# eth_a.net
KiCad netlist of a schematic drawn in Altium Designer
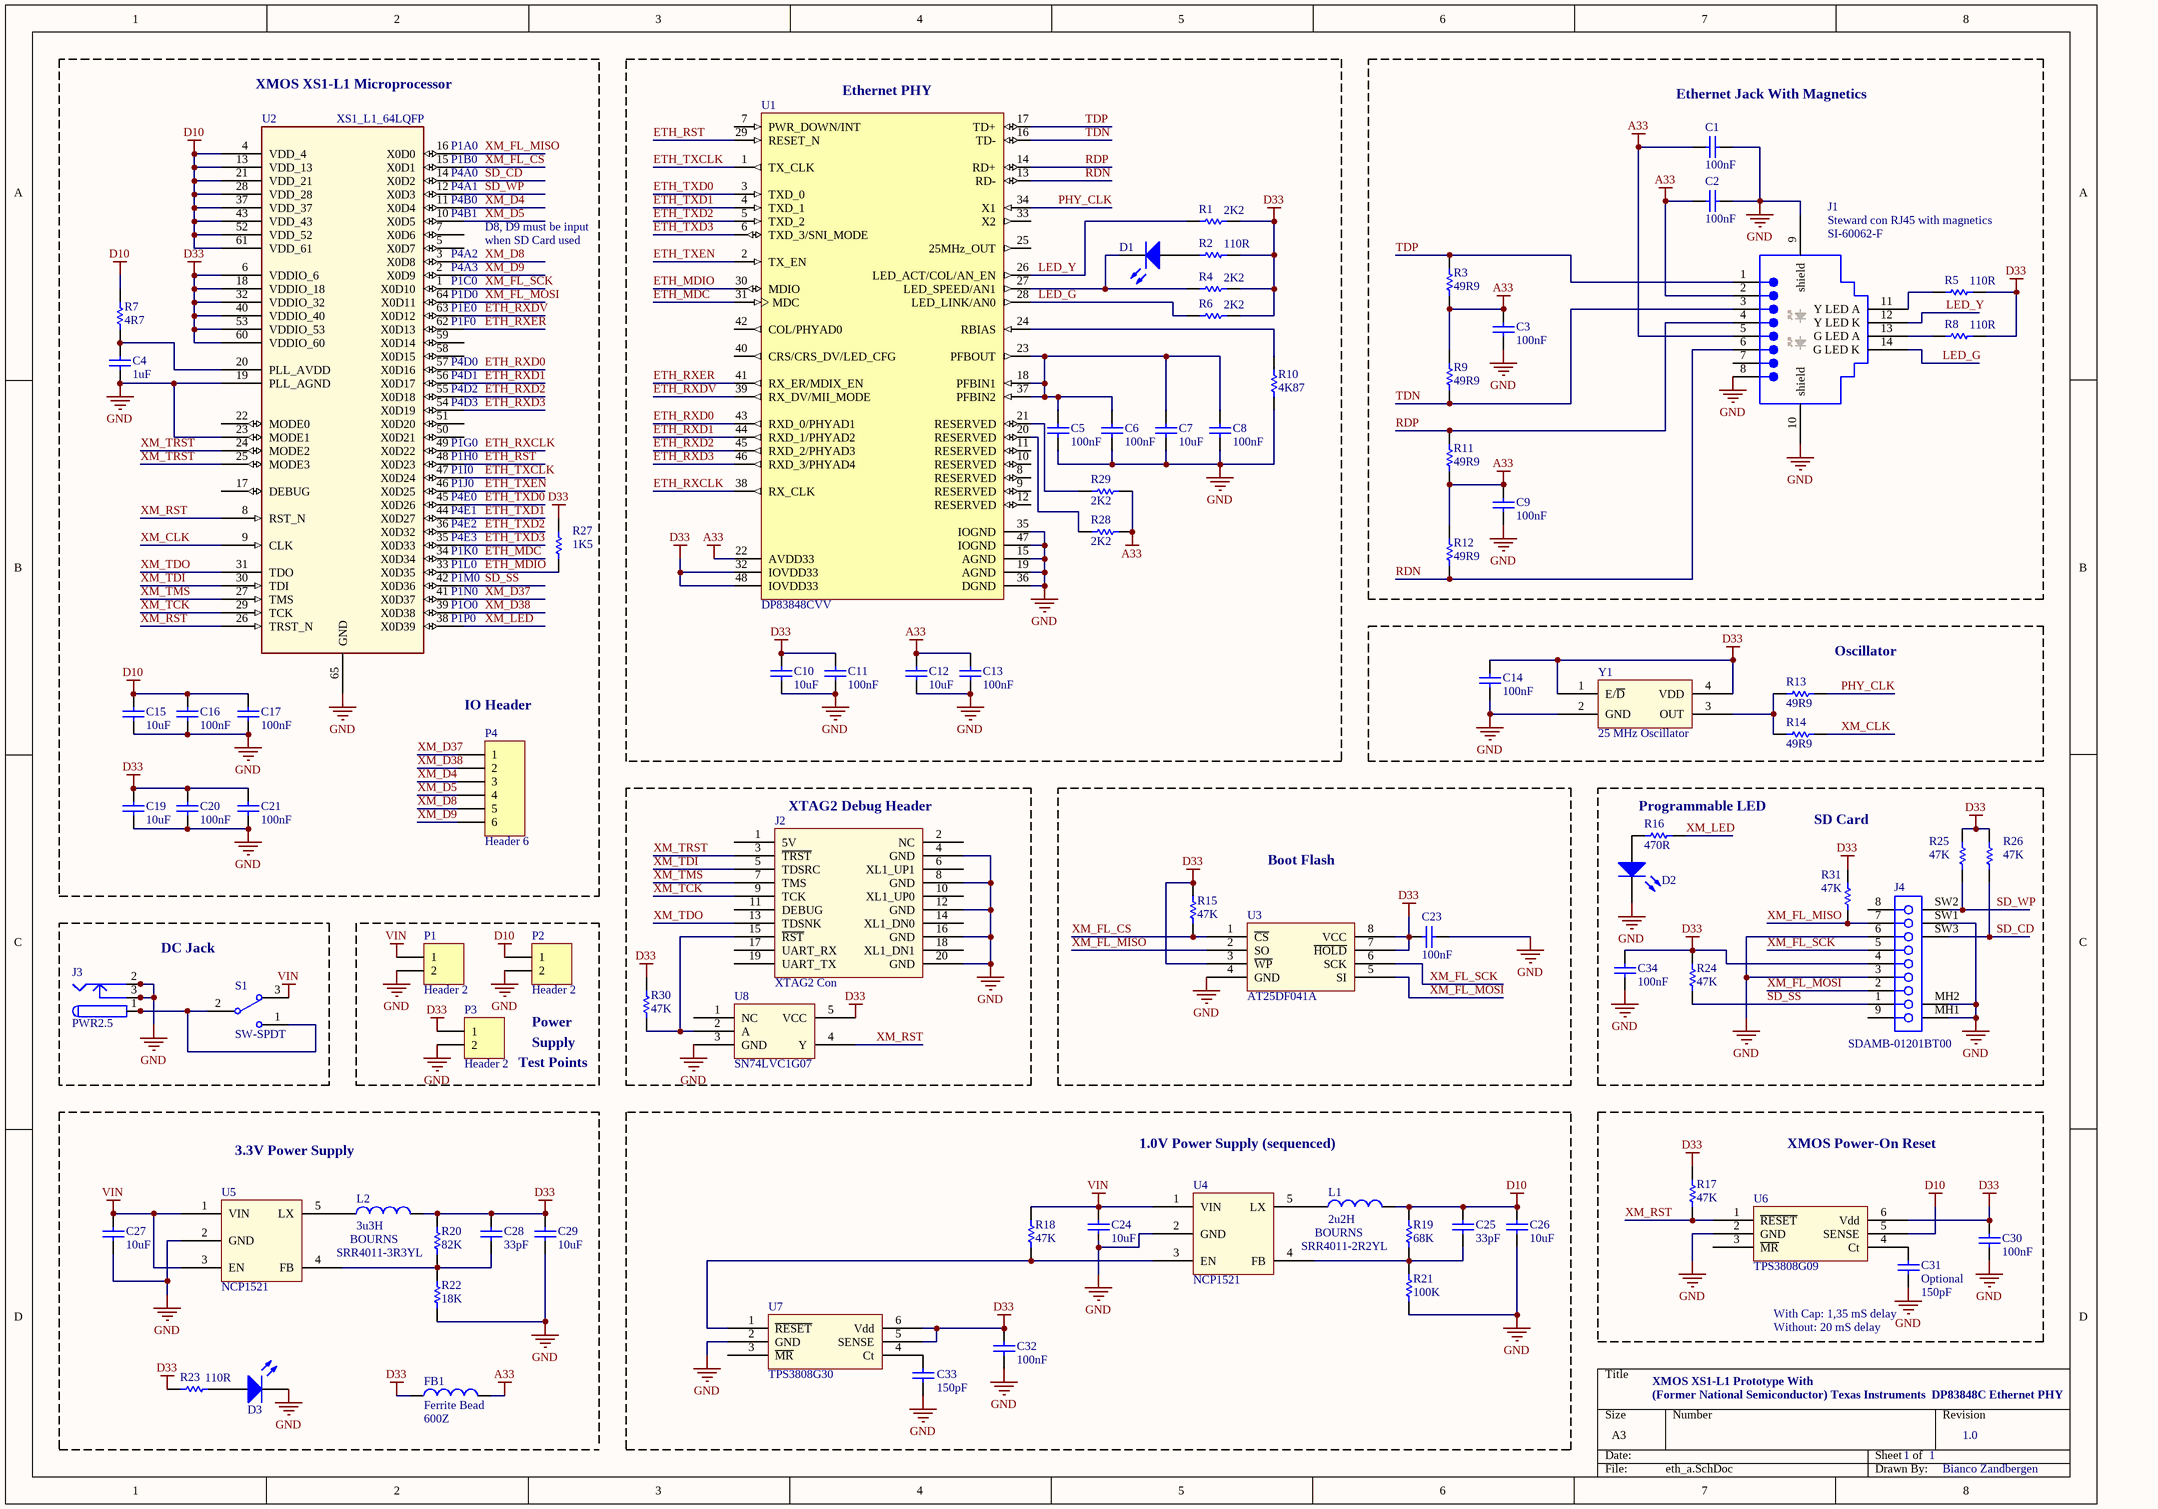
[diagram p0: eth_a.SchDoc]

(export (version "E")
  (design (tool "Eeschema 10.0.6"))
  (components
    (comp (ref "C1")
      (value "100nF")
      (footprint "1608[0603]_CAP")
      (description "Capacitor")
      (fields (field (name "Comment") "Cap"))
      (libsource (lib "xmos_common") (part "Cap"))
    )
    (comp (ref "C2")
      (value "100nF")
      (footprint "1608[0603]_CAP")
      (description "Capacitor")
      (fields (field (name "Comment") "Cap"))
      (libsource (lib "xmos_common") (part "Cap"))
    )
    (comp (ref "C3")
      (value "100nF")
      (footprint "1608[0603]_CAP")
      (description "Capacitor")
      (fields (field (name "Comment") "Cap"))
      (libsource (lib "xmos_common") (part "Cap"))
    )
    (comp (ref "C4")
      (value "1uF")
      (footprint "1608[0603]_CAP")
      (description "Capacitor")
      (fields (field (name "MANUFACTURER") "KEMET") (field (name "Comment") "Cap"))
      (libsource (lib "xmos_common") (part "Cap"))
    )
    (comp (ref "C5")
      (value "100nF")
      (footprint "1608[0603]_CAP")
      (description "Capacitor")
      (fields (field (name "Comment") "Cap"))
      (libsource (lib "xmos_common") (part "Cap"))
    )
    (comp (ref "C6")
      (value "100nF")
      (footprint "1608[0603]_CAP")
      (description "Capacitor")
      (fields (field (name "Comment") "Cap"))
      (libsource (lib "xmos_common") (part "Cap"))
    )
    (comp (ref "C7")
      (value "10uF")
      (footprint "2012[0805]_CAP")
      (description "Capacitor")
      (fields (field (name "Comment") "Cap"))
      (libsource (lib "xmos_common") (part "Cap"))
    )
    (comp (ref "C8")
      (value "100nF")
      (footprint "1608[0603]_CAP")
      (description "Capacitor")
      (fields (field (name "Comment") "Cap"))
      (libsource (lib "xmos_common") (part "Cap"))
    )
    (comp (ref "C9")
      (value "100nF")
      (footprint "1608[0603]_CAP")
      (description "Capacitor")
      (fields (field (name "Comment") "Cap"))
      (libsource (lib "xmos_common") (part "Cap"))
    )
    (comp (ref "C10")
      (value "10uF")
      (footprint "2012[0805]_CAP")
      (description "Capacitor")
      (fields (field (name "Comment") "Cap"))
      (libsource (lib "xmos_common") (part "Cap"))
    )
    (comp (ref "C11")
      (value "100nF")
      (footprint "1608[0603]_CAP")
      (description "Capacitor")
      (fields (field (name "Comment") "Cap"))
      (libsource (lib "xmos_common") (part "Cap"))
    )
    (comp (ref "C12")
      (value "10uF")
      (footprint "2012[0805]_CAP")
      (description "Capacitor")
      (fields (field (name "Comment") "Cap"))
      (libsource (lib "xmos_common") (part "Cap"))
    )
    (comp (ref "C13")
      (value "100nF")
      (footprint "1608[0603]_CAP")
      (description "Capacitor")
      (fields (field (name "Comment") "Cap"))
      (libsource (lib "xmos_common") (part "Cap"))
    )
    (comp (ref "C14")
      (value "100nF")
      (footprint "1608[0603]_CAP")
      (description "Capacitor")
      (fields (field (name "Comment") "Cap"))
      (libsource (lib "xmos_common") (part "Cap"))
    )
    (comp (ref "C15")
      (value "10uF")
      (footprint "2012[0805]_CAP")
      (description "Capacitor")
      (fields (field (name "MANUFACTURER") "AVX") (field (name "Comment") "Cap"))
      (libsource (lib "xmos_common") (part "Cap"))
    )
    (comp (ref "C16")
      (value "100nF")
      (footprint "1608[0603]_CAP")
      (description "Capacitor")
      (fields (field (name "MANUFACTURER") "MURATA") (field (name "Comment") "Cap"))
      (libsource (lib "xmos_common") (part "Cap"))
    )
    (comp (ref "C17")
      (value "100nF")
      (footprint "1608[0603]_CAP")
      (description "Capacitor")
      (fields (field (name "Comment") "Cap"))
      (libsource (lib "xmos_common") (part "Cap"))
    )
    (comp (ref "C19")
      (value "10uF")
      (footprint "2012[0805]_CAP")
      (description "Capacitor")
      (fields (field (name "Comment") "Cap"))
      (libsource (lib "xmos_common") (part "Cap"))
    )
    (comp (ref "C20")
      (value "100nF")
      (footprint "1608[0603]_CAP")
      (description "Capacitor")
      (fields (field (name "Comment") "Cap"))
      (libsource (lib "xmos_common") (part "Cap"))
    )
    (comp (ref "C21")
      (value "100nF")
      (footprint "1608[0603]_CAP")
      (description "Capacitor")
      (fields (field (name "Comment") "Cap"))
      (libsource (lib "xmos_common") (part "Cap"))
    )
    (comp (ref "C23")
      (value "100nF")
      (footprint "1608[0603]_CAP")
      (description "Capacitor")
      (fields (field (name "Comment") "Cap"))
      (libsource (lib "xmos_common") (part "Cap"))
    )
    (comp (ref "C24")
      (value "10uF")
      (footprint "2012[0805]_CAP")
      (description "Capacitor")
      (fields (field (name "Comment") "Cap"))
      (libsource (lib "xmos_common") (part "Cap"))
    )
    (comp (ref "C25")
      (value "33pF")
      (footprint "1608[0603]_CAP")
      (description "Capacitor")
      (fields (field (name "Comment") "Cap"))
      (libsource (lib "xmos_common") (part "Cap"))
    )
    (comp (ref "C26")
      (value "10uF")
      (footprint "2012[0805]_CAP")
      (description "Capacitor")
      (fields (field (name "Comment") "Cap"))
      (libsource (lib "xmos_common") (part "Cap"))
    )
    (comp (ref "C27")
      (value "10uF")
      (footprint "2012[0805]_CAP")
      (description "Capacitor")
      (fields (field (name "Comment") "Cap"))
      (libsource (lib "xmos_common") (part "Cap"))
    )
    (comp (ref "C28")
      (value "33pF")
      (footprint "1608[0603]_CAP")
      (description "Capacitor")
      (fields (field (name "MANUFACTURER") "MURATA") (field (name "Comment") "Cap"))
      (libsource (lib "xmos_common") (part "Cap"))
    )
    (comp (ref "C29")
      (value "10uF")
      (footprint "2012[0805]_CAP")
      (description "Capacitor")
      (fields (field (name "Comment") "Cap"))
      (libsource (lib "xmos_common") (part "Cap"))
    )
    (comp (ref "C30")
      (value "100nF")
      (footprint "1608[0603]_CAP")
      (description "Capacitor")
      (fields (field (name "Comment") "Cap"))
      (libsource (lib "xmos_common") (part "Cap"))
    )
    (comp (ref "C31")
      (value "Optional")
      (footprint "1608[0603]_CAP")
      (description "Capacitor")
      (fields (field (name "ALTIUM_VALUE") "150pF") (field (name "MANUFACTURER") "MURATA"))
      (libsource (lib "xmos_common") (part "Cap"))
    )
    (comp (ref "C32")
      (value "100nF")
      (footprint "1608[0603]_CAP")
      (description "Capacitor")
      (fields (field (name "Comment") "Cap"))
      (libsource (lib "xmos_common") (part "Cap"))
    )
    (comp (ref "C33")
      (value "150pF")
      (footprint "1608[0603]_CAP")
      (description "Capacitor")
      (fields (field (name "Comment") "Optional"))
      (libsource (lib "xmos_common") (part "Cap"))
    )
    (comp (ref "C34")
      (value "100nF")
      (footprint "1608[0603]_CAP")
      (description "Capacitor")
      (fields (field (name "Comment") "Cap"))
      (libsource (lib "xmos_common") (part "Cap"))
    )
    (comp (ref "D1")
      (value "LED3")
      (footprint "2012[0805]_LED")
      (description "SMD LED 0805")
      (fields (field (name "MANUFACTURER") "KINGBRIGHT"))
      (libsource (lib "xmos_common") (part "LED3"))
    )
    (comp (ref "D2")
      (value "LED3")
      (footprint "2012[0805]_LED")
      (description "SMD LED 0805")
      (libsource (lib "xmos_common") (part "LED3"))
    )
    (comp (ref "D3")
      (value "LED3")
      (footprint "2012[0805]_LED")
      (description "SMD LED 0805")
      (fields (field (name "MANUFACTURER") "KINGBRIGHT"))
      (libsource (lib "xmos_common") (part "LED3"))
    )
    (comp (ref "FB1")
      (value "Ferrite Bead")
      (footprint "1608[0603]_FB")
      (fields (field (name "ALTIUM_VALUE") "600Z") (field (name "MANUFACTURER") "MURATA"))
      (libsource (lib "xmos_common") (part "Ferrite Bead"))
    )
    (comp (ref "J1")
      (value "Steward con RJ45 with magnetics")
      (footprint "Steward Con RJ45")
      (description "Right Angle,RJ45-Keyed, Flange Mount PCB Jack")
      (fields (field (name "DETAILS") "SI-60062-F") (field (name "MANUFACTURER") "STEWART CONNECTOR"))
      (libsource (lib "xmos_common") (part "Steward con RJ45 with magnetics"))
    )
    (comp (ref "J2")
      (value "XTAG2 Con")
      (footprint "IDC2.54-V20D")
      (description "XTAG2 Connector")
      (fields (field (name "MANUFACTURER") "TYCO"))
      (libsource (lib "xmos_common") (part "XTAG2_CON"))
    )
    (comp (ref "J3")
      (value "PWR2.5")
      (footprint "KLD-0202")
      (description "Low Voltage Power Supply Connector")
      (fields (field (name "MANUFACTURER") "SWITCHCRAFT"))
      (libsource (lib "xmos_common") (part "PWR2.5"))
    )
    (comp (ref "J4")
      (value "SDAMB-01201BT00")
      (footprint "SDCARD-SDAMB-012")
      (description "Secure Digital Card Connector, Type A without Cover")
      (fields (field (name "MANUFACTURER") "MULTICOMP"))
      (libsource (lib "xmos_common") (part "SDAMB-01201BT00"))
    )
    (comp (ref "L1")
      (value "2u2H")
      (footprint "BOURNS_SRR4011")
      (description "Inductor")
      (fields (field (name "MANUFACTURER") "BOURNS") (field (name "PRODUCTCODE") "SRR4011-2R2YL"))
      (libsource (lib "xmos_common") (part "Inductor"))
    )
    (comp (ref "L2")
      (value "3u3H")
      (footprint "BOURNS_SRR4011")
      (description "Inductor")
      (fields (field (name "PRODUCTCODE") "SRR4011-3R3YL") (field (name "MANUFACTURER") "BOURNS"))
      (libsource (lib "xmos_common") (part "Inductor"))
    )
    (comp (ref "P1")
      (value "Header 2")
      (footprint "HDR1X2")
      (description "Header, 2-Pin")
      (libsource (lib "xmos_common") (part "Header 2"))
    )
    (comp (ref "P2")
      (value "Header 2")
      (footprint "HDR1X2")
      (description "Header, 2-Pin")
      (libsource (lib "xmos_common") (part "Header 2"))
    )
    (comp (ref "P3")
      (value "Header 2")
      (footprint "HDR1X2")
      (description "Header, 2-Pin")
      (libsource (lib "xmos_common") (part "Header 2"))
    )
    (comp (ref "P4")
      (value "Header 6")
      (footprint "HDR1X6")
      (description "Header, 6-Pin")
      (libsource (lib "xmos_common") (part "Header 6"))
    )
    (comp (ref "R1")
      (value "2K2")
      (footprint "1608[0603]_RES")
      (description "Resistor")
      (fields (field (name "MANUFACTURER") "YAGEO") (field (name "Comment") "Res"))
      (libsource (lib "xmos_common") (part "Res"))
    )
    (comp (ref "R2")
      (value "110R")
      (footprint "1608[0603]_RES")
      (description "Resistor")
      (fields (field (name "Comment") "Res"))
      (libsource (lib "xmos_common") (part "Res"))
    )
    (comp (ref "R3")
      (value "49R9")
      (footprint "1608[0603]_RES")
      (description "Resistor")
      (fields (field (name "MANUFACTURER") "SUSUMU") (field (name "Comment") "Res"))
      (libsource (lib "xmos_common") (part "Res"))
    )
    (comp (ref "R4")
      (value "2K2")
      (footprint "1608[0603]_RES")
      (description "Resistor")
      (fields (field (name "Comment") "Res"))
      (libsource (lib "xmos_common") (part "Res"))
    )
    (comp (ref "R5")
      (value "110R")
      (footprint "1608[0603]_RES")
      (description "Resistor")
      (fields (field (name "MANUFACTURER") "PANASONIC") (field (name "Comment") "Res"))
      (libsource (lib "xmos_common") (part "Res"))
    )
    (comp (ref "R6")
      (value "2K2")
      (footprint "1608[0603]_RES")
      (description "Resistor")
      (fields (field (name "Comment") "Res"))
      (libsource (lib "xmos_common") (part "Res"))
    )
    (comp (ref "R7")
      (value "4R7")
      (footprint "1608[0603]_RES")
      (description "Resistor")
      (fields (field (name "MANUFACTURER") "PANASONIC") (field (name "Comment") "Res"))
      (libsource (lib "xmos_common") (part "Res"))
    )
    (comp (ref "R8")
      (value "110R")
      (footprint "1608[0603]_RES")
      (description "Resistor")
      (fields (field (name "Comment") "Res"))
      (libsource (lib "xmos_common") (part "Res"))
    )
    (comp (ref "R9")
      (value "49R9")
      (footprint "1608[0603]_RES")
      (description "Resistor")
      (fields (field (name "Comment") "Res"))
      (libsource (lib "xmos_common") (part "Res"))
    )
    (comp (ref "R10")
      (value "4K87")
      (footprint "1608[0603]_RES")
      (description "Resistor")
      (fields (field (name "MANUFACTURER") "MULTICOMP") (field (name "Comment") "Res"))
      (libsource (lib "xmos_common") (part "Res"))
    )
    (comp (ref "R11")
      (value "49R9")
      (footprint "1608[0603]_RES")
      (description "Resistor")
      (fields (field (name "Comment") "Res"))
      (libsource (lib "xmos_common") (part "Res"))
    )
    (comp (ref "R12")
      (value "49R9")
      (footprint "1608[0603]_RES")
      (description "Resistor")
      (fields (field (name "Comment") "Res"))
      (libsource (lib "xmos_common") (part "Res"))
    )
    (comp (ref "R13")
      (value "49R9")
      (footprint "1608[0603]_RES")
      (description "Resistor")
      (fields (field (name "Comment") "Res"))
      (libsource (lib "xmos_common") (part "Res"))
    )
    (comp (ref "R14")
      (value "49R9")
      (footprint "1608[0603]_RES")
      (description "Resistor")
      (fields (field (name "Comment") "Res"))
      (libsource (lib "xmos_common") (part "Res"))
    )
    (comp (ref "R15")
      (value "47K")
      (footprint "1608[0603]_RES")
      (description "Resistor")
      (fields (field (name "MANUFACTURER") "VISHAY DRALORIC") (field (name "Comment") "Res"))
      (libsource (lib "xmos_common") (part "Res"))
    )
    (comp (ref "R16")
      (value "470R")
      (footprint "1608[0603]_RES")
      (description "Resistor")
      (fields (field (name "MANUFACTURER") "BOURNS") (field (name "Comment") "Res"))
      (libsource (lib "xmos_common") (part "Res"))
    )
    (comp (ref "R17")
      (value "47K")
      (footprint "1608[0603]_RES")
      (description "Resistor")
      (fields (field (name "Comment") "Res"))
      (libsource (lib "xmos_common") (part "Res"))
    )
    (comp (ref "R18")
      (value "47K")
      (footprint "1608[0603]_RES")
      (description "Resistor")
      (fields (field (name "Comment") "Res"))
      (libsource (lib "xmos_common") (part "Res"))
    )
    (comp (ref "R19")
      (value "68K")
      (footprint "1608[0603]_RES")
      (description "Resistor")
      (fields (field (name "MANUFACTURER") "PANASONIC") (field (name "Comment") "Res"))
      (libsource (lib "xmos_common") (part "Res"))
    )
    (comp (ref "R20")
      (value "82K")
      (footprint "1608[0603]_RES")
      (description "Resistor")
      (fields (field (name "MANUFACTURER") "VISHAY DRALORIC") (field (name "Comment") "Res"))
      (libsource (lib "xmos_common") (part "Res"))
    )
    (comp (ref "R21")
      (value "100K")
      (footprint "1608[0603]_RES")
      (description "Resistor")
      (fields (field (name "MANUFACTURER") "VISHAY DRALORIC") (field (name "Comment") "Res"))
      (libsource (lib "xmos_common") (part "Res"))
    )
    (comp (ref "R22")
      (value "18K")
      (footprint "1608[0603]_RES")
      (description "Resistor")
      (fields (field (name "MANUFACTURER") "VISHAY DRALORIC") (field (name "Comment") "Res"))
      (libsource (lib "xmos_common") (part "Res"))
    )
    (comp (ref "R23")
      (value "110R")
      (footprint "1608[0603]_RES")
      (description "Resistor")
      (fields (field (name "Comment") "Res"))
      (libsource (lib "xmos_common") (part "Res"))
    )
    (comp (ref "R24")
      (value "47K")
      (footprint "1608[0603]_RES")
      (description "Resistor")
      (fields (field (name "Comment") "Res"))
      (libsource (lib "xmos_common") (part "Res"))
    )
    (comp (ref "R25")
      (value "47K")
      (footprint "1608[0603]_RES")
      (description "Resistor")
      (fields (field (name "Comment") "Res"))
      (libsource (lib "xmos_common") (part "Res"))
    )
    (comp (ref "R26")
      (value "47K")
      (footprint "1608[0603]_RES")
      (description "Resistor")
      (fields (field (name "Comment") "Res"))
      (libsource (lib "xmos_common") (part "Res"))
    )
    (comp (ref "R27")
      (value "1K5")
      (footprint "1608[0603]_RES")
      (description "Resistor")
      (fields (field (name "MANUFACTURER") "PANASONIC") (field (name "Comment") "Res"))
      (libsource (lib "xmos_common") (part "Res"))
    )
    (comp (ref "R28")
      (value "2K2")
      (footprint "1608[0603]_RES")
      (description "Resistor")
      (fields (field (name "Comment") "Res"))
      (libsource (lib "xmos_common") (part "Res"))
    )
    (comp (ref "R29")
      (value "2K2")
      (footprint "1608[0603]_RES")
      (description "Resistor")
      (fields (field (name "Comment") "Res"))
      (libsource (lib "xmos_common") (part "Res"))
    )
    (comp (ref "R30")
      (value "47K")
      (footprint "1608[0603]_RES")
      (description "Resistor")
      (fields (field (name "Comment") "Res"))
      (libsource (lib "xmos_common") (part "Res"))
    )
    (comp (ref "R31")
      (value "47K")
      (footprint "1608[0603]_RES")
      (description "Resistor")
      (fields (field (name "Comment") "Res"))
      (libsource (lib "xmos_common") (part "Res"))
    )
    (comp (ref "S1")
      (value "SW-SPDT")
      (footprint "SIP-3")
      (description "SPDT Switch")
      (fields (field (name "MANUFACTURER") "EAO"))
      (libsource (lib "xmos_common") (part "SW-SPDT"))
    )
    (comp (ref "U1")
      (value "DP83848CVV")
      (footprint "TSQFP50P900X900-48M")
      (description "Single Port 10/100 Mb/s Ethernet PHY")
      (fields (field (name "MANUFACTURER") "National Semiconductor"))
      (libsource (lib "xmos_common") (part "DP83848CVV"))
    )
    (comp (ref "U2")
      (value "XS1_L1_64LQFP")
      (footprint "XMOS_QFP50P1200X1200X160-65N")
      (description "XMOS XS1-L1 Microprocessor")
      (fields (field (name "MANUFACTURER") "XMOS"))
      (libsource (lib "xmos_common") (part "XS1_L1_64LQFP"))
    )
    (comp (ref "U3")
      (value "AT25DF041A")
      (footprint "SOIC150-8_M")
      (description "4Mbit SPI Flash")
      (fields (field (name "MANUFACTURER") "ATMEL"))
      (libsource (lib "xmos_common") (part "AT25DF041A"))
    )
    (comp (ref "U4")
      (value "NCP1521")
      (footprint "SOT23-5")
      (description "Buck Converter")
      (libsource (lib "xmos_common") (part "NCP1521"))
    )
    (comp (ref "U5")
      (value "NCP1521")
      (footprint "SOT23-5")
      (description "Buck Converter")
      (fields (field (name "MANUFACTURER") "ON SEMICONDUCTOR"))
      (libsource (lib "xmos_common") (part "NCP1521"))
    )
    (comp (ref "U6")
      (value "TPS3808G09")
      (footprint "SOT23-6")
      (description "Power on Reset controller 0.9V")
      (fields (field (name "MANUFACTURER") "TEXAS INSTRUMENTS"))
      (libsource (lib "xmos_common") (part "TPS3808G09"))
    )
    (comp (ref "U7")
      (value "TPS3808G30")
      (footprint "SOT23-6")
      (description "Power on Reset controller 3.0V")
      (fields (field (name "MANUFACTURER") "TEXAS INSTRUMENTS"))
      (libsource (lib "xmos_common") (part "TPS3808G30"))
    )
    (comp (ref "U8")
      (value "SN74LVC1G07")
      (footprint "SOT23-5")
      (description "Buffer (open drain output)")
      (fields (field (name "MANUFACTURER") "TEXAS INSTRUMENTS"))
      (libsource (lib "xmos_common") (part "SN74LVC1G07"))
    )
    (comp (ref "Y1")
      (value "25 MHz Oscillator")
      (footprint "OSC_32_50")
      (description "Crystal Oscillator SMD 5mm x 3.2mm")
      (fields (field (name "MANUFACTURER") "TXC"))
      (libsource (lib "xmos_common") (part "oscillator"))
    )
  )
  (nets
    (net (code "1") (name "/ETH_MDC") (class "Default")
      (node (ref "U1") (pin "31") (pinfunction "MDC_31") (pintype "input"))
      (node (ref "U2") (pin "34") (pinfunction "X0D34_34") (pintype "bidirectional"))
    )
    (net (code "2") (name "/ETH_MDIO") (class "Default")
      (node (ref "R27") (pin "1") (pinfunction "1_1") (pintype "passive"))
      (node (ref "U1") (pin "30") (pinfunction "MDIO_30") (pintype "bidirectional"))
      (node (ref "U2") (pin "33") (pinfunction "X0D35_33") (pintype "bidirectional"))
    )
    (net (code "3") (name "/ETH_RST") (class "Default")
      (node (ref "U1") (pin "29") (pinfunction "RESET_N_29") (pintype "input"))
      (node (ref "U2") (pin "48") (pinfunction "X0D23_48") (pintype "bidirectional"))
    )
    (net (code "4") (name "/ETH_RXCLK") (class "Default")
      (node (ref "U1") (pin "38") (pinfunction "RX_CLK_38") (pintype "output"))
      (node (ref "U2") (pin "49") (pinfunction "X0D22_49") (pintype "bidirectional"))
    )
    (net (code "5") (name "/ETH_RXD0") (class "Default")
      (node (ref "U1") (pin "43") (pinfunction "RXD_0/PHYAD1_43") (pintype "output"))
      (node (ref "U2") (pin "57") (pinfunction "X0D16_57") (pintype "bidirectional"))
    )
    (net (code "6") (name "/ETH_RXD1") (class "Default")
      (node (ref "U1") (pin "44") (pinfunction "RXD_1/PHYAD2_44") (pintype "output"))
      (node (ref "U2") (pin "56") (pinfunction "X0D17_56") (pintype "bidirectional"))
    )
    (net (code "7") (name "/ETH_RXD2") (class "Default")
      (node (ref "U1") (pin "45") (pinfunction "RXD_2/PHYAD3_45") (pintype "output"))
      (node (ref "U2") (pin "55") (pinfunction "X0D18_55") (pintype "bidirectional"))
    )
    (net (code "8") (name "/ETH_RXD3") (class "Default")
      (node (ref "U1") (pin "46") (pinfunction "RXD_3/PHYAD4_46") (pintype "output"))
      (node (ref "U2") (pin "54") (pinfunction "X0D19_54") (pintype "bidirectional"))
    )
    (net (code "9") (name "/ETH_RXDV") (class "Default")
      (node (ref "U1") (pin "39") (pinfunction "RX_DV/MII_MODE_39") (pintype "output"))
      (node (ref "U2") (pin "63") (pinfunction "X0D12_63") (pintype "bidirectional"))
    )
    (net (code "10") (name "/ETH_RXER") (class "Default")
      (node (ref "U1") (pin "41") (pinfunction "RX_ER/MDIX_EN_41") (pintype "output"))
      (node (ref "U2") (pin "62") (pinfunction "X0D13_62") (pintype "bidirectional"))
    )
    (net (code "11") (name "/ETH_TXCLK") (class "Default")
      (node (ref "U1") (pin "1") (pinfunction "TX_CLK_1") (pintype "output"))
      (node (ref "U2") (pin "47") (pinfunction "X0D24_47") (pintype "bidirectional"))
    )
    (net (code "12") (name "/ETH_TXD0") (class "Default")
      (node (ref "U1") (pin "3") (pinfunction "TXD_0_3") (pintype "input"))
      (node (ref "U2") (pin "45") (pinfunction "X0D26_45") (pintype "bidirectional"))
    )
    (net (code "13") (name "/ETH_TXD1") (class "Default")
      (node (ref "U1") (pin "4") (pinfunction "TXD_1_4") (pintype "input"))
      (node (ref "U2") (pin "44") (pinfunction "X0D27_44") (pintype "bidirectional"))
    )
    (net (code "14") (name "/ETH_TXD2") (class "Default")
      (node (ref "U1") (pin "5") (pinfunction "TXD_2_5") (pintype "input"))
      (node (ref "U2") (pin "36") (pinfunction "X0D32_36") (pintype "bidirectional"))
    )
    (net (code "15") (name "/ETH_TXD3") (class "Default")
      (node (ref "U1") (pin "6") (pinfunction "TXD_3/SNI_MODE_6") (pintype "bidirectional"))
      (node (ref "U2") (pin "35") (pinfunction "X0D33_35") (pintype "bidirectional"))
    )
    (net (code "16") (name "/ETH_TXEN") (class "Default")
      (node (ref "U1") (pin "2") (pinfunction "TX_EN_2") (pintype "input"))
      (node (ref "U2") (pin "46") (pinfunction "X0D25_46") (pintype "bidirectional"))
    )
    (net (code "17") (name "/LED_G") (class "Default")
      (node (ref "J1") (pin "14") (pinfunction "G_LED_K_14") (pintype "passive"))
      (node (ref "R6") (pin "1") (pinfunction "1_1") (pintype "passive"))
      (node (ref "U1") (pin "28") (pinfunction "LED_LINK/AN0_28") (pintype "output"))
    )
    (net (code "18") (name "/LED_Y") (class "Default")
      (node (ref "J1") (pin "12") (pinfunction "Y_LED_K_12") (pintype "passive"))
      (node (ref "R1") (pin "1") (pinfunction "1_1") (pintype "passive"))
      (node (ref "U1") (pin "26") (pinfunction "LED_ACT/COL/AN_EN_26") (pintype "output"))
    )
    (net (code "19") (name "/PHY_CLK") (class "Default")
      (node (ref "R13") (pin "1") (pinfunction "1_1") (pintype "passive"))
      (node (ref "U1") (pin "34") (pinfunction "X1_34") (pintype "input"))
    )
    (net (code "20") (name "/RDN") (class "Default")
      (node (ref "J1") (pin "6") (pinfunction "6_6") (pintype "passive"))
      (node (ref "R12") (pin "1") (pinfunction "1_1") (pintype "passive"))
      (node (ref "U1") (pin "13") (pinfunction "RD-_13") (pintype "bidirectional"))
    )
    (net (code "21") (name "/RDP") (class "Default")
      (node (ref "J1") (pin "4") (pinfunction "4_4") (pintype "passive"))
      (node (ref "R11") (pin "2") (pinfunction "2_2") (pintype "passive"))
      (node (ref "U1") (pin "14") (pinfunction "RD+_14") (pintype "bidirectional"))
    )
    (net (code "22") (name "/SD_CD") (class "Default")
      (node (ref "J4") (pin "SW3") (pinfunction "SW3_SW3") (pintype "passive"))
      (node (ref "R26") (pin "1") (pinfunction "1_1") (pintype "passive"))
      (node (ref "U2") (pin "14") (pinfunction "X0D2_14") (pintype "bidirectional"))
    )
    (net (code "23") (name "/SD_SS") (class "Default")
      (node (ref "J4") (pin "1") (pinfunction "1_1") (pintype "passive"))
      (node (ref "R24") (pin "1") (pinfunction "1_1") (pintype "passive"))
      (node (ref "U2") (pin "42") (pinfunction "X0D36_42") (pintype "bidirectional"))
    )
    (net (code "24") (name "/SD_WP") (class "Default")
      (node (ref "J4") (pin "SW2") (pinfunction "SW2_SW2") (pintype "passive"))
      (node (ref "R25") (pin "1") (pinfunction "1_1") (pintype "passive"))
      (node (ref "U2") (pin "12") (pinfunction "X0D3_12") (pintype "bidirectional"))
    )
    (net (code "25") (name "/TDN") (class "Default")
      (node (ref "J1") (pin "3") (pinfunction "3_3") (pintype "passive"))
      (node (ref "R9") (pin "1") (pinfunction "1_1") (pintype "passive"))
      (node (ref "U1") (pin "16") (pinfunction "TD-_16") (pintype "bidirectional"))
    )
    (net (code "26") (name "/TDP") (class "Default")
      (node (ref "J1") (pin "1") (pinfunction "1_1") (pintype "passive"))
      (node (ref "R3") (pin "2") (pinfunction "2_2") (pintype "passive"))
      (node (ref "U1") (pin "17") (pinfunction "TD+_17") (pintype "bidirectional"))
    )
    (net (code "27") (name "/XM_CLK") (class "Default")
      (node (ref "R14") (pin "1") (pinfunction "1_1") (pintype "passive"))
      (node (ref "U2") (pin "9") (pinfunction "CLK_9") (pintype "input"))
    )
    (net (code "28") (name "/XM_D4") (class "Default")
      (node (ref "P4") (pin "3") (pinfunction "3_3") (pintype "passive"))
      (node (ref "U2") (pin "11") (pinfunction "X0D4_11") (pintype "bidirectional"))
    )
    (net (code "29") (name "/XM_D5") (class "Default")
      (node (ref "P4") (pin "4") (pinfunction "4_4") (pintype "passive"))
      (node (ref "U2") (pin "10") (pinfunction "X0D5_10") (pintype "bidirectional"))
    )
    (net (code "30") (name "/XM_D8") (class "Default")
      (node (ref "P4") (pin "5") (pinfunction "5_5") (pintype "passive"))
      (node (ref "U2") (pin "3") (pinfunction "X0D8_3") (pintype "bidirectional"))
    )
    (net (code "31") (name "/XM_D9") (class "Default")
      (node (ref "P4") (pin "6") (pinfunction "6_6") (pintype "passive"))
      (node (ref "U2") (pin "2") (pinfunction "X0D9_2") (pintype "bidirectional"))
    )
    (net (code "32") (name "/XM_D37") (class "Default")
      (node (ref "P4") (pin "1") (pinfunction "1_1") (pintype "passive"))
      (node (ref "U2") (pin "41") (pinfunction "X0D37_41") (pintype "bidirectional"))
    )
    (net (code "33") (name "/XM_D38") (class "Default")
      (node (ref "P4") (pin "2") (pinfunction "2_2") (pintype "passive"))
      (node (ref "U2") (pin "39") (pinfunction "X0D38_39") (pintype "bidirectional"))
    )
    (net (code "34") (name "/XM_FL_CS") (class "Default")
      (node (ref "R15") (pin "1") (pinfunction "1_1") (pintype "passive"))
      (node (ref "U2") (pin "15") (pinfunction "X0D1_15") (pintype "bidirectional"))
      (node (ref "U3") (pin "1") (pinfunction "~{CS}_1") (pintype "passive"))
    )
    (net (code "35") (name "/XM_FL_MISO") (class "Default")
      (node (ref "J4") (pin "7") (pinfunction "7_7") (pintype "passive"))
      (node (ref "R31") (pin "1") (pinfunction "1_1") (pintype "passive"))
      (node (ref "U2") (pin "16") (pinfunction "X0D0_16") (pintype "bidirectional"))
      (node (ref "U3") (pin "2") (pinfunction "SO_2") (pintype "passive"))
    )
    (net (code "36") (name "/XM_FL_MOSI") (class "Default")
      (node (ref "J4") (pin "2") (pinfunction "2_2") (pintype "passive"))
      (node (ref "U2") (pin "64") (pinfunction "X0D11_64") (pintype "bidirectional"))
      (node (ref "U3") (pin "5") (pinfunction "SI_5") (pintype "passive"))
    )
    (net (code "37") (name "/XM_FL_SCK") (class "Default")
      (node (ref "J4") (pin "5") (pinfunction "5_5") (pintype "passive"))
      (node (ref "U2") (pin "1") (pinfunction "X0D10_1") (pintype "bidirectional"))
      (node (ref "U3") (pin "6") (pinfunction "SCK_6") (pintype "passive"))
    )
    (net (code "38") (name "/XM_LED") (class "Default")
      (node (ref "R16") (pin "1") (pinfunction "1_1") (pintype "passive"))
      (node (ref "U2") (pin "38") (pinfunction "X0D39_38") (pintype "bidirectional"))
    )
    (net (code "39") (name "/XM_RST") (class "Default")
      (node (ref "R17") (pin "1") (pinfunction "1_1") (pintype "passive"))
      (node (ref "U2") (pin "26") (pinfunction "TRST_N_26") (pintype "input"))
      (node (ref "U2") (pin "8") (pinfunction "RST_N_8") (pintype "input"))
      (node (ref "U6") (pin "1") (pinfunction "~{RESET}_1") (pintype "passive"))
      (node (ref "U8") (pin "4") (pinfunction "Y_4") (pintype "passive"))
    )
    (net (code "40") (name "/XM_TCK") (class "Default")
      (node (ref "J2") (pin "9") (pinfunction "TCK_9") (pintype "passive"))
      (node (ref "U2") (pin "29") (pinfunction "TCK_29") (pintype "input"))
    )
    (net (code "41") (name "/XM_TDI") (class "Default")
      (node (ref "J2") (pin "5") (pinfunction "TDSRC_5") (pintype "passive"))
      (node (ref "U2") (pin "30") (pinfunction "TDI_30") (pintype "input"))
    )
    (net (code "42") (name "/XM_TDO") (class "Default")
      (node (ref "J2") (pin "13") (pinfunction "TDSNK_13") (pintype "passive"))
      (node (ref "U2") (pin "31") (pinfunction "TDO_31") (pintype "tri_state"))
    )
    (net (code "43") (name "/XM_TMS") (class "Default")
      (node (ref "J2") (pin "7") (pinfunction "TMS_7") (pintype "passive"))
      (node (ref "U2") (pin "27") (pinfunction "TMS_27") (pintype "input"))
    )
    (net (code "44") (name "/XM_TRST") (class "Default")
      (node (ref "J2") (pin "3") (pinfunction "~{TRST}_3") (pintype "passive"))
      (node (ref "U2") (pin "24") (pinfunction "MODE2_24") (pintype "bidirectional"))
      (node (ref "U2") (pin "25") (pinfunction "MODE3_25") (pintype "bidirectional"))
    )
    (net (code "45") (name "A33") (class "Default")
      (node (ref "C1") (pin "2") (pinfunction "2_2") (pintype "passive"))
      (node (ref "C12") (pin "2") (pinfunction "2_2") (pintype "passive"))
      (node (ref "C13") (pin "2") (pinfunction "2_2") (pintype "passive"))
      (node (ref "C2") (pin "2") (pinfunction "2_2") (pintype "passive"))
      (node (ref "C3") (pin "2") (pinfunction "2_2") (pintype "passive"))
      (node (ref "C9") (pin "2") (pinfunction "2_2") (pintype "passive"))
      (node (ref "FB1") (pin "2") (pinfunction "2_2") (pintype "passive"))
      (node (ref "J1") (pin "2") (pinfunction "2_2") (pintype "passive"))
      (node (ref "J1") (pin "5") (pinfunction "5_5") (pintype "passive"))
      (node (ref "R11") (pin "1") (pinfunction "1_1") (pintype "passive"))
      (node (ref "R12") (pin "2") (pinfunction "2_2") (pintype "passive"))
      (node (ref "R28") (pin "2") (pinfunction "2_2") (pintype "passive"))
      (node (ref "R29") (pin "2") (pinfunction "2_2") (pintype "passive"))
      (node (ref "R3") (pin "1") (pinfunction "1_1") (pintype "passive"))
      (node (ref "R9") (pin "2") (pinfunction "2_2") (pintype "passive"))
      (node (ref "U1") (pin "22") (pinfunction "AVDD33_22") (pintype "power_in"))
    )
    (net (code "46") (name "D10") (class "Default")
      (node (ref "C15") (pin "2") (pinfunction "2_2") (pintype "passive"))
      (node (ref "C16") (pin "2") (pinfunction "2_2") (pintype "passive"))
      (node (ref "C17") (pin "2") (pinfunction "2_2") (pintype "passive"))
      (node (ref "C25") (pin "2") (pinfunction "2_2") (pintype "passive"))
      (node (ref "C26") (pin "2") (pinfunction "2_2") (pintype "passive"))
      (node (ref "L1") (pin "2") (pinfunction "2_2") (pintype "passive"))
      (node (ref "P2") (pin "1") (pinfunction "1_1") (pintype "passive"))
      (node (ref "R19") (pin "2") (pinfunction "2_2") (pintype "passive"))
      (node (ref "R7") (pin "2") (pinfunction "2_2") (pintype "passive"))
      (node (ref "U2") (pin "13") (pinfunction "VDD_13_13") (pintype "passive"))
      (node (ref "U2") (pin "21") (pinfunction "VDD_21_21") (pintype "passive"))
      (node (ref "U2") (pin "28") (pinfunction "VDD_28_28") (pintype "passive"))
      (node (ref "U2") (pin "37") (pinfunction "VDD_37_37") (pintype "passive"))
      (node (ref "U2") (pin "4") (pinfunction "VDD_4_4") (pintype "passive"))
      (node (ref "U2") (pin "43") (pinfunction "VDD_43_43") (pintype "passive"))
      (node (ref "U2") (pin "52") (pinfunction "VDD_52_52") (pintype "passive"))
      (node (ref "U2") (pin "61") (pinfunction "VDD_61_61") (pintype "passive"))
      (node (ref "U6") (pin "5") (pinfunction "SENSE_5") (pintype "passive"))
    )
    (net (code "47") (name "D33") (class "Default")
      (node (ref "C10") (pin "2") (pinfunction "2_2") (pintype "passive"))
      (node (ref "C11") (pin "2") (pinfunction "2_2") (pintype "passive"))
      (node (ref "C14") (pin "2") (pinfunction "2_2") (pintype "passive"))
      (node (ref "C19") (pin "2") (pinfunction "2_2") (pintype "passive"))
      (node (ref "C20") (pin "2") (pinfunction "2_2") (pintype "passive"))
      (node (ref "C21") (pin "2") (pinfunction "2_2") (pintype "passive"))
      (node (ref "C23") (pin "2") (pinfunction "2_2") (pintype "passive"))
      (node (ref "C28") (pin "2") (pinfunction "2_2") (pintype "passive"))
      (node (ref "C29") (pin "2") (pinfunction "2_2") (pintype "passive"))
      (node (ref "C30") (pin "2") (pinfunction "2_2") (pintype "passive"))
      (node (ref "C32") (pin "2") (pinfunction "2_2") (pintype "passive"))
      (node (ref "C34") (pin "2") (pinfunction "2_2") (pintype "passive"))
      (node (ref "FB1") (pin "1") (pinfunction "1_1") (pintype "passive"))
      (node (ref "J4") (pin "4") (pinfunction "4_4") (pintype "passive"))
      (node (ref "L2") (pin "2") (pinfunction "2_2") (pintype "passive"))
      (node (ref "P3") (pin "1") (pinfunction "1_1") (pintype "passive"))
      (node (ref "R1") (pin "2") (pinfunction "2_2") (pintype "passive"))
      (node (ref "R15") (pin "2") (pinfunction "2_2") (pintype "passive"))
      (node (ref "R17") (pin "2") (pinfunction "2_2") (pintype "passive"))
      (node (ref "R2") (pin "2") (pinfunction "2_2") (pintype "passive"))
      (node (ref "R20") (pin "2") (pinfunction "2_2") (pintype "passive"))
      (node (ref "R23") (pin "1") (pinfunction "1_1") (pintype "passive"))
      (node (ref "R24") (pin "2") (pinfunction "2_2") (pintype "passive"))
      (node (ref "R25") (pin "2") (pinfunction "2_2") (pintype "passive"))
      (node (ref "R26") (pin "2") (pinfunction "2_2") (pintype "passive"))
      (node (ref "R27") (pin "2") (pinfunction "2_2") (pintype "passive"))
      (node (ref "R30") (pin "2") (pinfunction "2_2") (pintype "passive"))
      (node (ref "R31") (pin "2") (pinfunction "2_2") (pintype "passive"))
      (node (ref "R4") (pin "2") (pinfunction "2_2") (pintype "passive"))
      (node (ref "R5") (pin "2") (pinfunction "2_2") (pintype "passive"))
      (node (ref "R6") (pin "2") (pinfunction "2_2") (pintype "passive"))
      (node (ref "R8") (pin "2") (pinfunction "2_2") (pintype "passive"))
      (node (ref "U1") (pin "32") (pinfunction "IOVDD33_32") (pintype "power_in"))
      (node (ref "U1") (pin "48") (pinfunction "IOVDD33_48") (pintype "power_in"))
      (node (ref "U2") (pin "18") (pinfunction "VDDIO_18_18") (pintype "passive"))
      (node (ref "U2") (pin "32") (pinfunction "VDDIO_32_32") (pintype "passive"))
      (node (ref "U2") (pin "40") (pinfunction "VDDIO_40_40") (pintype "passive"))
      (node (ref "U2") (pin "53") (pinfunction "VDDIO_53_53") (pintype "passive"))
      (node (ref "U2") (pin "6") (pinfunction "VDDIO_6_6") (pintype "passive"))
      (node (ref "U2") (pin "60") (pinfunction "VDDIO_60_60") (pintype "passive"))
      (node (ref "U3") (pin "3") (pinfunction "~{WP}_3") (pintype "passive"))
      (node (ref "U3") (pin "7") (pinfunction "~{HOLD}_7") (pintype "passive"))
      (node (ref "U3") (pin "8") (pinfunction "VCC_8") (pintype "passive"))
      (node (ref "U6") (pin "6") (pinfunction "Vdd_6") (pintype "passive"))
      (node (ref "U7") (pin "5") (pinfunction "SENSE_5") (pintype "passive"))
      (node (ref "U7") (pin "6") (pinfunction "Vdd_6") (pintype "passive"))
      (node (ref "U8") (pin "5") (pinfunction "VCC_5") (pintype "passive"))
      (node (ref "Y1") (pin "1") (pinfunction "E/~{D}_1") (pintype "passive"))
      (node (ref "Y1") (pin "4") (pinfunction "VDD_4") (pintype "passive"))
    )
    (net (code "48") (name "GND") (class "Default")
      (node (ref "C1") (pin "1") (pinfunction "1_1") (pintype "passive"))
      (node (ref "C10") (pin "1") (pinfunction "1_1") (pintype "passive"))
      (node (ref "C11") (pin "1") (pinfunction "1_1") (pintype "passive"))
      (node (ref "C12") (pin "1") (pinfunction "1_1") (pintype "passive"))
      (node (ref "C13") (pin "1") (pinfunction "1_1") (pintype "passive"))
      (node (ref "C14") (pin "1") (pinfunction "1_1") (pintype "passive"))
      (node (ref "C15") (pin "1") (pinfunction "1_1") (pintype "passive"))
      (node (ref "C16") (pin "1") (pinfunction "1_1") (pintype "passive"))
      (node (ref "C17") (pin "1") (pinfunction "1_1") (pintype "passive"))
      (node (ref "C19") (pin "1") (pinfunction "1_1") (pintype "passive"))
      (node (ref "C2") (pin "1") (pinfunction "1_1") (pintype "passive"))
      (node (ref "C20") (pin "1") (pinfunction "1_1") (pintype "passive"))
      (node (ref "C21") (pin "1") (pinfunction "1_1") (pintype "passive"))
      (node (ref "C23") (pin "1") (pinfunction "1_1") (pintype "passive"))
      (node (ref "C24") (pin "1") (pinfunction "1_1") (pintype "passive"))
      (node (ref "C26") (pin "1") (pinfunction "1_1") (pintype "passive"))
      (node (ref "C27") (pin "1") (pinfunction "1_1") (pintype "passive"))
      (node (ref "C29") (pin "1") (pinfunction "1_1") (pintype "passive"))
      (node (ref "C3") (pin "1") (pinfunction "1_1") (pintype "passive"))
      (node (ref "C30") (pin "1") (pinfunction "1_1") (pintype "passive"))
      (node (ref "C31") (pin "1") (pinfunction "1_1") (pintype "passive"))
      (node (ref "C32") (pin "1") (pinfunction "1_1") (pintype "passive"))
      (node (ref "C33") (pin "1") (pinfunction "1_1") (pintype "passive"))
      (node (ref "C34") (pin "1") (pinfunction "1_1") (pintype "passive"))
      (node (ref "C4") (pin "1") (pinfunction "1_1") (pintype "passive"))
      (node (ref "C5") (pin "1") (pinfunction "1_1") (pintype "passive"))
      (node (ref "C6") (pin "1") (pinfunction "1_1") (pintype "passive"))
      (node (ref "C7") (pin "1") (pinfunction "1_1") (pintype "passive"))
      (node (ref "C8") (pin "1") (pinfunction "1_1") (pintype "passive"))
      (node (ref "C9") (pin "1") (pinfunction "1_1") (pintype "passive"))
      (node (ref "D2") (pin "2") (pinfunction "K_2") (pintype "passive"))
      (node (ref "D3") (pin "2") (pinfunction "K_2") (pintype "passive"))
      (node (ref "J1") (pin "10") (pinfunction "shield_10") (pintype "passive"))
      (node (ref "J1") (pin "8") (pinfunction "8_8") (pintype "passive"))
      (node (ref "J1") (pin "9") (pinfunction "shield_9") (pintype "passive"))
      (node (ref "J2") (pin "12") (pinfunction "GND_12") (pintype "passive"))
      (node (ref "J2") (pin "16") (pinfunction "GND_16") (pintype "passive"))
      (node (ref "J2") (pin "20") (pinfunction "GND_20") (pintype "passive"))
      (node (ref "J2") (pin "4") (pinfunction "GND_4") (pintype "passive"))
      (node (ref "J2") (pin "8") (pinfunction "GND_8") (pintype "passive"))
      (node (ref "J3") (pin "2") (pinfunction "2_2") (pintype "power_in"))
      (node (ref "J3") (pin "2A") (pinfunction "2A_2A") (pintype "power_in"))
      (node (ref "J3") (pin "2B") (pinfunction "2B_2B") (pintype "power_in"))
      (node (ref "J3") (pin "3") (pinfunction "3_3") (pintype "power_in"))
      (node (ref "J3") (pin "3A") (pinfunction "3A_3A") (pintype "power_in"))
      (node (ref "J3") (pin "3B") (pinfunction "3B_3B") (pintype "power_in"))
      (node (ref "J4") (pin "3") (pinfunction "3_3") (pintype "passive"))
      (node (ref "J4") (pin "6") (pinfunction "6_6") (pintype "passive"))
      (node (ref "J4") (pin "MH1") (pinfunction "MH1_MH1") (pintype "passive"))
      (node (ref "J4") (pin "MH2") (pinfunction "MH2_MH2") (pintype "passive"))
      (node (ref "J4") (pin "SW1") (pinfunction "SW1_SW1") (pintype "passive"))
      (node (ref "P1") (pin "2") (pinfunction "2_2") (pintype "passive"))
      (node (ref "P2") (pin "2") (pinfunction "2_2") (pintype "passive"))
      (node (ref "P3") (pin "2") (pinfunction "2_2") (pintype "passive"))
      (node (ref "R10") (pin "1") (pinfunction "1_1") (pintype "passive"))
      (node (ref "R21") (pin "1") (pinfunction "1_1") (pintype "passive"))
      (node (ref "R22") (pin "1") (pinfunction "1_1") (pintype "passive"))
      (node (ref "U1") (pin "15") (pinfunction "AGND_15") (pintype "power_in"))
      (node (ref "U1") (pin "19") (pinfunction "AGND_19") (pintype "power_in"))
      (node (ref "U1") (pin "35") (pinfunction "IOGND_35") (pintype "power_in"))
      (node (ref "U1") (pin "36") (pinfunction "DGND_36") (pintype "power_in"))
      (node (ref "U1") (pin "47") (pinfunction "IOGND_47") (pintype "power_in"))
      (node (ref "U2") (pin "19") (pinfunction "PLL_AGND_19") (pintype "passive"))
      (node (ref "U2") (pin "23") (pinfunction "MODE1_23") (pintype "bidirectional"))
      (node (ref "U2") (pin "65") (pinfunction "GND_65") (pintype "passive"))
      (node (ref "U3") (pin "4") (pinfunction "GND_4") (pintype "passive"))
      (node (ref "U4") (pin "2") (pinfunction "GND_2") (pintype "passive"))
      (node (ref "U5") (pin "2") (pinfunction "GND_2") (pintype "passive"))
      (node (ref "U6") (pin "2") (pinfunction "GND_2") (pintype "passive"))
      (node (ref "U7") (pin "2") (pinfunction "GND_2") (pintype "passive"))
      (node (ref "U8") (pin "3") (pinfunction "GND_3") (pintype "passive"))
      (node (ref "Y1") (pin "2") (pinfunction "GND_2") (pintype "passive"))
    )
    (net (code "49") (name "Net-(D1-A)") (class "Default")
      (node (ref "D1") (pin "1") (pinfunction "A_1") (pintype "passive"))
      (node (ref "R2") (pin "1") (pinfunction "1_1") (pintype "passive"))
    )
    (net (code "50") (name "Net-(D1-K)") (class "Default")
      (node (ref "D1") (pin "2") (pinfunction "K_2") (pintype "passive"))
      (node (ref "R4") (pin "1") (pinfunction "1_1") (pintype "passive"))
      (node (ref "U1") (pin "27") (pinfunction "LED_SPEED/AN1_27") (pintype "output"))
    )
    (net (code "51") (name "Net-(D2-A)") (class "Default")
      (node (ref "D2") (pin "1") (pinfunction "A_1") (pintype "passive"))
      (node (ref "R16") (pin "2") (pinfunction "2_2") (pintype "passive"))
    )
    (net (code "52") (name "Net-(D3-A)") (class "Default")
      (node (ref "D3") (pin "1") (pinfunction "A_1") (pintype "passive"))
      (node (ref "R23") (pin "2") (pinfunction "2_2") (pintype "passive"))
    )
    (net (code "53") (name "Net-(J1-G_LED_A)") (class "Default")
      (node (ref "J1") (pin "13") (pinfunction "G_LED_A_13") (pintype "passive"))
      (node (ref "R8") (pin "1") (pinfunction "1_1") (pintype "passive"))
    )
    (net (code "54") (name "Net-(J1-Y_LED_A)") (class "Default")
      (node (ref "J1") (pin "11") (pinfunction "Y_LED_A_11") (pintype "passive"))
      (node (ref "R5") (pin "1") (pinfunction "1_1") (pintype "passive"))
    )
    (net (code "55") (name "Net-(J2-~{RST})") (class "Default")
      (node (ref "J2") (pin "15") (pinfunction "~{RST}_15") (pintype "passive"))
      (node (ref "R30") (pin "1") (pinfunction "1_1") (pintype "passive"))
      (node (ref "U8") (pin "2") (pinfunction "A_2") (pintype "passive"))
    )
    (net (code "56") (name "Net-(J3-Pad1)") (class "Default")
      (node (ref "J3") (pin "1") (pinfunction "1_1") (pintype "power_in"))
      (node (ref "J3") (pin "1A") (pinfunction "1A_1A") (pintype "power_in"))
      (node (ref "J3") (pin "1B") (pinfunction "1B_1B") (pintype "power_in"))
      (node (ref "S1") (pin "1") (pinfunction "1_1") (pintype "passive"))
      (node (ref "S1") (pin "2") (pinfunction "2_2") (pintype "passive"))
    )
    (net (code "57") (name "Net-(R28-Pad1)") (class "Default")
      (node (ref "R28") (pin "1") (pinfunction "1_1") (pintype "passive"))
      (node (ref "U1") (pin "20") (pinfunction "RESERVED_20") (pintype "bidirectional"))
    )
    (net (code "58") (name "Net-(R29-Pad1)") (class "Default")
      (node (ref "R29") (pin "1") (pinfunction "1_1") (pintype "passive"))
      (node (ref "U1") (pin "21") (pinfunction "RESERVED_21") (pintype "bidirectional"))
    )
    (net (code "59") (name "Net-(U1-PFBIN1)") (class "Default")
      (node (ref "C5") (pin "2") (pinfunction "2_2") (pintype "passive"))
      (node (ref "C6") (pin "2") (pinfunction "2_2") (pintype "passive"))
      (node (ref "C7") (pin "2") (pinfunction "2_2") (pintype "passive"))
      (node (ref "C8") (pin "2") (pinfunction "2_2") (pintype "passive"))
      (node (ref "U1") (pin "18") (pinfunction "PFBIN1_18") (pintype "input"))
      (node (ref "U1") (pin "23") (pinfunction "PFBOUT_23") (pintype "output"))
      (node (ref "U1") (pin "37") (pinfunction "PFBIN2_37") (pintype "input"))
    )
    (net (code "60") (name "Net-(U1-RBIAS)") (class "Default")
      (node (ref "R10") (pin "2") (pinfunction "2_2") (pintype "passive"))
      (node (ref "U1") (pin "24") (pinfunction "RBIAS_24") (pintype "input"))
    )
    (net (code "61") (name "Net-(U2-PLL_AVDD)") (class "Default")
      (node (ref "C4") (pin "2") (pinfunction "2_2") (pintype "passive"))
      (node (ref "R7") (pin "1") (pinfunction "1_1") (pintype "passive"))
      (node (ref "U2") (pin "20") (pinfunction "PLL_AVDD_20") (pintype "passive"))
    )
    (net (code "62") (name "Net-(U4-EN)") (class "Default")
      (node (ref "R18") (pin "1") (pinfunction "1_1") (pintype "passive"))
      (node (ref "U4") (pin "3") (pinfunction "EN_3") (pintype "passive"))
      (node (ref "U7") (pin "1") (pinfunction "~{RESET}_1") (pintype "passive"))
    )
    (net (code "63") (name "Net-(U4-FB)") (class "Default")
      (node (ref "C25") (pin "1") (pinfunction "1_1") (pintype "passive"))
      (node (ref "R19") (pin "1") (pinfunction "1_1") (pintype "passive"))
      (node (ref "R21") (pin "2") (pinfunction "2_2") (pintype "passive"))
      (node (ref "U4") (pin "4") (pinfunction "FB_4") (pintype "passive"))
    )
    (net (code "64") (name "Net-(U4-LX)") (class "Default")
      (node (ref "L1") (pin "1") (pinfunction "1_1") (pintype "passive"))
      (node (ref "U4") (pin "5") (pinfunction "LX_5") (pintype "passive"))
    )
    (net (code "65") (name "Net-(U5-FB)") (class "Default")
      (node (ref "C28") (pin "1") (pinfunction "1_1") (pintype "passive"))
      (node (ref "R20") (pin "1") (pinfunction "1_1") (pintype "passive"))
      (node (ref "R22") (pin "2") (pinfunction "2_2") (pintype "passive"))
      (node (ref "U5") (pin "4") (pinfunction "FB_4") (pintype "passive"))
    )
    (net (code "66") (name "Net-(U5-LX)") (class "Default")
      (node (ref "L2") (pin "1") (pinfunction "1_1") (pintype "passive"))
      (node (ref "U5") (pin "5") (pinfunction "LX_5") (pintype "passive"))
    )
    (net (code "67") (name "Net-(U6-Ct)") (class "Default")
      (node (ref "C31") (pin "2") (pinfunction "2_2") (pintype "passive"))
      (node (ref "U6") (pin "4") (pinfunction "Ct_4") (pintype "passive"))
    )
    (net (code "68") (name "Net-(U7-Ct)") (class "Default")
      (node (ref "C33") (pin "2") (pinfunction "2_2") (pintype "passive"))
      (node (ref "U7") (pin "4") (pinfunction "Ct_4") (pintype "passive"))
    )
    (net (code "69") (name "Net-(Y1-OUT)") (class "Default")
      (node (ref "R13") (pin "2") (pinfunction "2_2") (pintype "passive"))
      (node (ref "R14") (pin "2") (pinfunction "2_2") (pintype "passive"))
      (node (ref "Y1") (pin "3") (pinfunction "OUT_3") (pintype "passive"))
    )
    (net (code "70") (name "VIN") (class "Default")
      (node (ref "C24") (pin "2") (pinfunction "2_2") (pintype "passive"))
      (node (ref "C27") (pin "2") (pinfunction "2_2") (pintype "passive"))
      (node (ref "P1") (pin "1") (pinfunction "1_1") (pintype "passive"))
      (node (ref "R18") (pin "2") (pinfunction "2_2") (pintype "passive"))
      (node (ref "S1") (pin "3") (pinfunction "3_3") (pintype "passive"))
      (node (ref "U4") (pin "1") (pinfunction "VIN_1") (pintype "passive"))
      (node (ref "U5") (pin "1") (pinfunction "VIN_1") (pintype "passive"))
      (node (ref "U5") (pin "3") (pinfunction "EN_3") (pintype "passive"))
    )
    (net (code "71") (name "unconnected-(J1-Pad7)") (class "Default")
      (node (ref "J1") (pin "7") (pinfunction "7_7") (pintype "passive"))
    )
    (net (code "72") (name "unconnected-(J2-5V-Pad1)") (class "Default")
      (node (ref "J2") (pin "1") (pinfunction "5V_1") (pintype "passive"))
    )
    (net (code "73") (name "unconnected-(J2-DEBUG-Pad11)") (class "Default")
      (node (ref "J2") (pin "11") (pinfunction "DEBUG_11") (pintype "passive"))
    )
    (net (code "74") (name "unconnected-(J2-NC-Pad2)") (class "Default")
      (node (ref "J2") (pin "2") (pinfunction "NC_2") (pintype "passive"))
    )
    (net (code "75") (name "unconnected-(J2-UART_RX-Pad17)") (class "Default")
      (node (ref "J2") (pin "17") (pinfunction "UART_RX_17") (pintype "passive"))
    )
    (net (code "76") (name "unconnected-(J2-UART_TX-Pad19)") (class "Default")
      (node (ref "J2") (pin "19") (pinfunction "UART_TX_19") (pintype "passive"))
    )
    (net (code "77") (name "unconnected-(J2-XL1_DN0-Pad14)") (class "Default")
      (node (ref "J2") (pin "14") (pinfunction "XL1_DN0_14") (pintype "passive"))
    )
    (net (code "78") (name "unconnected-(J2-XL1_DN1-Pad18)") (class "Default")
      (node (ref "J2") (pin "18") (pinfunction "XL1_DN1_18") (pintype "passive"))
    )
    (net (code "79") (name "unconnected-(J2-XL1_UP0-Pad10)") (class "Default")
      (node (ref "J2") (pin "10") (pinfunction "XL1_UP0_10") (pintype "passive"))
    )
    (net (code "80") (name "unconnected-(J2-XL1_UP1-Pad6)") (class "Default")
      (node (ref "J2") (pin "6") (pinfunction "XL1_UP1_6") (pintype "passive"))
    )
    (net (code "81") (name "unconnected-(J4-Pad8)") (class "Default")
      (node (ref "J4") (pin "8") (pinfunction "8_8") (pintype "passive"))
    )
    (net (code "82") (name "unconnected-(J4-Pad9)") (class "Default")
      (node (ref "J4") (pin "9") (pinfunction "9_9") (pintype "passive"))
    )
    (net (code "83") (name "unconnected-(U1-25MHz_OUT-Pad25)") (class "Default")
      (node (ref "U1") (pin "25") (pinfunction "25MHz_OUT_25") (pintype "output"))
    )
    (net (code "84") (name "unconnected-(U1-COL{slash}PHYAD0-Pad42)") (class "Default")
      (node (ref "U1") (pin "42") (pinfunction "COL/PHYAD0_42") (pintype "output"))
    )
    (net (code "85") (name "unconnected-(U1-CRS{slash}CRS_DV{slash}LED_CFG-Pad40)") (class "Default")
      (node (ref "U1") (pin "40") (pinfunction "CRS/CRS_DV/LED_CFG_40") (pintype "output"))
    )
    (net (code "86") (name "unconnected-(U1-PWR_DOWN{slash}INT-Pad7)") (class "Default")
      (node (ref "U1") (pin "7") (pinfunction "PWR_DOWN/INT_7") (pintype "input"))
    )
    (net (code "87") (name "unconnected-(U1-RESERVED-Pad8)") (class "Default")
      (node (ref "U1") (pin "8") (pinfunction "RESERVED_8") (pintype "bidirectional"))
    )
    (net (code "88") (name "unconnected-(U1-RESERVED-Pad9)") (class "Default")
      (node (ref "U1") (pin "9") (pinfunction "RESERVED_9") (pintype "bidirectional"))
    )
    (net (code "89") (name "unconnected-(U1-RESERVED-Pad10)") (class "Default")
      (node (ref "U1") (pin "10") (pinfunction "RESERVED_10") (pintype "bidirectional"))
    )
    (net (code "90") (name "unconnected-(U1-RESERVED-Pad11)") (class "Default")
      (node (ref "U1") (pin "11") (pinfunction "RESERVED_11") (pintype "bidirectional"))
    )
    (net (code "91") (name "unconnected-(U1-RESERVED-Pad12)") (class "Default")
      (node (ref "U1") (pin "12") (pinfunction "RESERVED_12") (pintype "bidirectional"))
    )
    (net (code "92") (name "unconnected-(U1-X2-Pad33)") (class "Default")
      (node (ref "U1") (pin "33") (pinfunction "X2_33") (pintype "output"))
    )
    (net (code "93") (name "unconnected-(U2-DEBUG-Pad17)") (class "Default")
      (node (ref "U2") (pin "17") (pinfunction "DEBUG_17") (pintype "bidirectional"))
    )
    (net (code "94") (name "unconnected-(U2-MODE0-Pad22)") (class "Default")
      (node (ref "U2") (pin "22") (pinfunction "MODE0_22") (pintype "bidirectional"))
    )
    (net (code "95") (name "unconnected-(U2-X0D6-Pad7)") (class "Default")
      (node (ref "U2") (pin "7") (pinfunction "X0D6_7") (pintype "bidirectional"))
    )
    (net (code "96") (name "unconnected-(U2-X0D7-Pad5)") (class "Default")
      (node (ref "U2") (pin "5") (pinfunction "X0D7_5") (pintype "bidirectional"))
    )
    (net (code "97") (name "unconnected-(U2-X0D14-Pad59)") (class "Default")
      (node (ref "U2") (pin "59") (pinfunction "X0D14_59") (pintype "bidirectional"))
    )
    (net (code "98") (name "unconnected-(U2-X0D15-Pad58)") (class "Default")
      (node (ref "U2") (pin "58") (pinfunction "X0D15_58") (pintype "bidirectional"))
    )
    (net (code "99") (name "unconnected-(U2-X0D20-Pad51)") (class "Default")
      (node (ref "U2") (pin "51") (pinfunction "X0D20_51") (pintype "bidirectional"))
    )
    (net (code "100") (name "unconnected-(U2-X0D21-Pad50)") (class "Default")
      (node (ref "U2") (pin "50") (pinfunction "X0D21_50") (pintype "bidirectional"))
    )
    (net (code "101") (name "unconnected-(U6-~{MR}-Pad3)") (class "Default")
      (node (ref "U6") (pin "3") (pinfunction "~{MR}_3") (pintype "passive"))
    )
    (net (code "102") (name "unconnected-(U7-~{MR}-Pad3)") (class "Default")
      (node (ref "U7") (pin "3") (pinfunction "~{MR}_3") (pintype "passive"))
    )
    (net (code "103") (name "unconnected-(U8-NC-Pad1)") (class "Default")
      (node (ref "U8") (pin "1") (pinfunction "NC_1") (pintype "passive"))
    )
  )
)
